# RelayBypass.net
KiCad netlist of a schematic drawn in EAGLE
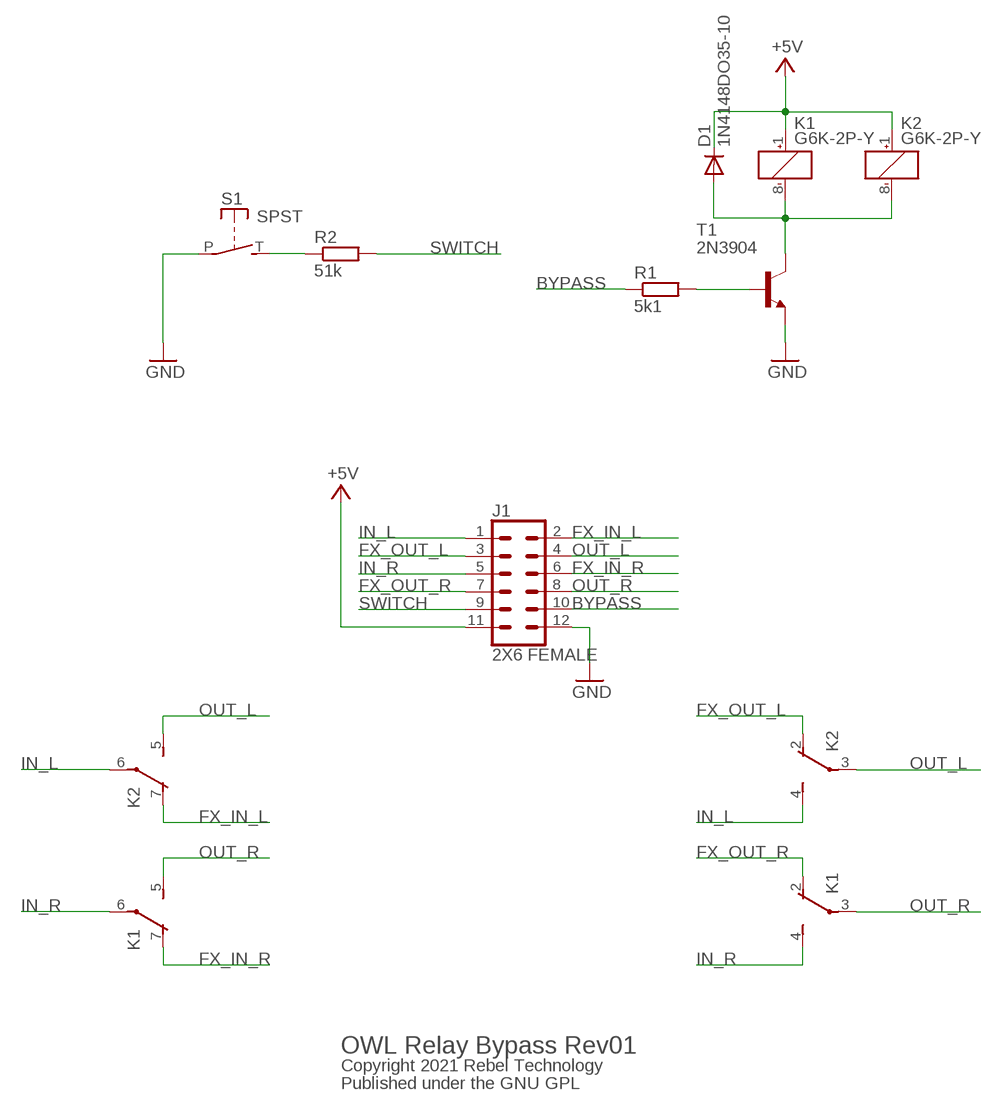
[diagram p0: schematic, sheet 1]

(export (version "E")
  (design (tool "Eeschema 10.0.6"))
  (components
    (comp (ref "D1")
      (value "1N4148DO35-10")
      (footprint "eagle-import:DO35-10")
      (libsource (lib "eagle-import") (part "1N4148DO35-10"))
    )
    (comp (ref "J1")
      (value "2X6 FEMALE")
      (footprint "eagle-import:2X6")
      (libsource (lib "eagle-import") (part "CONN_06X2PTH_FEMALE"))
    )
    (comp (ref "K1")
      (value "G6K-2P-Y")
      (footprint "eagle-import:G6K-2P-Y")
      (fields (field (name "MF") "OMRON COMPONENTS USA") (field (name "MPN") "G6K-2P-Y DC12"))
      (libsource (lib "eagle-import") (part "G6K-2P-Y"))
    )
    (comp (ref "K2")
      (value "G6K-2P-Y")
      (footprint "eagle-import:G6K-2P-Y")
      (fields (field (name "MF") "OMRON COMPONENTS USA") (field (name "MPN") "G6K-2P-Y DC12"))
      (libsource (lib "eagle-import") (part "G6K-2P-Y"))
    )
    (comp (ref "R1")
      (value "5k1")
      (footprint "eagle-import:0204_7")
      (libsource (lib "eagle-import") (part "R-EU_0204/7"))
    )
    (comp (ref "R2")
      (value "51k")
      (footprint "eagle-import:0204_7")
      (libsource (lib "eagle-import") (part "R-EU_0204/7"))
    )
    (comp (ref "S1")
      (value "SPST")
      (footprint "eagle-import:JUDCOSPST")
      (libsource (lib "eagle-import") (part "SPST"))
    )
    (comp (ref "T1")
      (value "2N3904")
      (footprint "eagle-import:TO92")
      (libsource (lib "eagle-import") (part "2N3904"))
    )
  )
  (nets
    (net (code "1") (name "+5V") (class "Default")
      (node (ref "D1") (pin "C") (pinfunction "C_C") (pintype "passive"))
      (node (ref "J1") (pin "11") (pinfunction "11_11") (pintype "passive"))
      (node (ref "K1") (pin "1") (pinfunction "+_1") (pintype "passive"))
      (node (ref "K2") (pin "1") (pinfunction "+_1") (pintype "passive"))
    )
    (net (code "2") (name "/BYPASS") (class "Default")
      (node (ref "J1") (pin "10") (pinfunction "10_10") (pintype "passive"))
      (node (ref "R1") (pin "1") (pinfunction "1_1") (pintype "passive"))
    )
    (net (code "3") (name "/FX_IN_L") (class "Default")
      (node (ref "J1") (pin "2") (pinfunction "2_2") (pintype "passive"))
      (node (ref "K2") (pin "7") (pinfunction "O_7") (pintype "passive"))
    )
    (net (code "4") (name "/FX_IN_R") (class "Default")
      (node (ref "J1") (pin "6") (pinfunction "6_6") (pintype "passive"))
      (node (ref "K1") (pin "7") (pinfunction "O_7") (pintype "passive"))
    )
    (net (code "5") (name "/FX_OUT_L") (class "Default")
      (node (ref "J1") (pin "3") (pinfunction "3_3") (pintype "passive"))
      (node (ref "K2") (pin "2") (pinfunction "O_2") (pintype "passive"))
    )
    (net (code "6") (name "/FX_OUT_R") (class "Default")
      (node (ref "J1") (pin "7") (pinfunction "7_7") (pintype "passive"))
      (node (ref "K1") (pin "2") (pinfunction "O_2") (pintype "passive"))
    )
    (net (code "7") (name "/IN_L") (class "Default")
      (node (ref "J1") (pin "1") (pinfunction "1_1") (pintype "passive"))
      (node (ref "K2") (pin "4") (pinfunction "S_4") (pintype "passive"))
      (node (ref "K2") (pin "6") (pinfunction "P_6") (pintype "passive"))
    )
    (net (code "8") (name "/IN_R") (class "Default")
      (node (ref "J1") (pin "5") (pinfunction "5_5") (pintype "passive"))
      (node (ref "K1") (pin "4") (pinfunction "S_4") (pintype "passive"))
      (node (ref "K1") (pin "6") (pinfunction "P_6") (pintype "passive"))
    )
    (net (code "9") (name "/OUT_L") (class "Default")
      (node (ref "J1") (pin "4") (pinfunction "4_4") (pintype "passive"))
      (node (ref "K2") (pin "3") (pinfunction "P_3") (pintype "passive"))
      (node (ref "K2") (pin "5") (pinfunction "S_5") (pintype "passive"))
    )
    (net (code "10") (name "/OUT_R") (class "Default")
      (node (ref "J1") (pin "8") (pinfunction "8_8") (pintype "passive"))
      (node (ref "K1") (pin "3") (pinfunction "P_3") (pintype "passive"))
      (node (ref "K1") (pin "5") (pinfunction "S_5") (pintype "passive"))
    )
    (net (code "11") (name "/SWITCH") (class "Default")
      (node (ref "J1") (pin "9") (pinfunction "9_9") (pintype "passive"))
      (node (ref "R2") (pin "2") (pinfunction "2_2") (pintype "passive"))
    )
    (net (code "12") (name "GND") (class "Default")
      (node (ref "J1") (pin "12") (pinfunction "12_12") (pintype "passive"))
      (node (ref "S1") (pin "P") (pinfunction "P_P") (pintype "passive"))
      (node (ref "T1") (pin "3") (pinfunction "E_3") (pintype "passive"))
    )
    (net (code "13") (name "Net-(K1A--)") (class "Default")
      (node (ref "D1") (pin "A") (pinfunction "A_A") (pintype "passive"))
      (node (ref "K1") (pin "8") (pinfunction "-_8") (pintype "passive"))
      (node (ref "K2") (pin "8") (pinfunction "-_8") (pintype "passive"))
      (node (ref "T1") (pin "1") (pinfunction "C_1") (pintype "passive"))
    )
    (net (code "14") (name "Net-(S1-S)") (class "Default")
      (node (ref "R2") (pin "1") (pinfunction "1_1") (pintype "passive"))
      (node (ref "S1") (pin "T") (pinfunction "S_T") (pintype "passive"))
    )
    (net (code "15") (name "Net-(T1-B)") (class "Default")
      (node (ref "R1") (pin "2") (pinfunction "2_2") (pintype "passive"))
      (node (ref "T1") (pin "2") (pinfunction "B_2") (pintype "passive"))
    )
  )
)
